# OSD_Shield.net
KiCad netlist of a schematic drawn in EAGLE
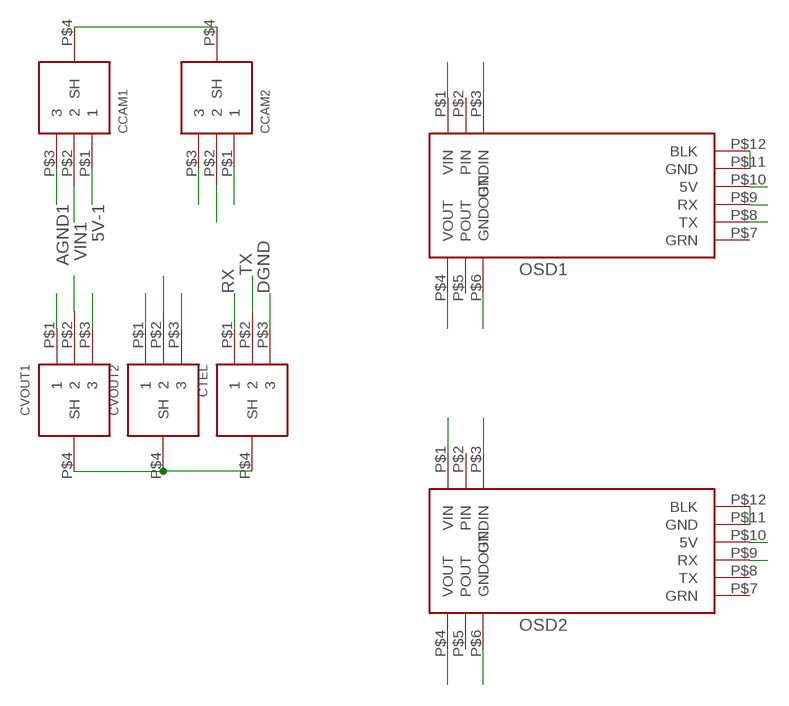
[diagram p0: schematic, sheet 1]

(export (version "E")
  (design (tool "Eeschema 10.0.6"))
  (components
    (comp (ref "CCAM1")
      (value "TRA3M")
      (footprint "eagle-import:TRA3M")
      (libsource (lib "eagle-import") (part "TRA3M"))
    )
    (comp (ref "CCAM2")
      (value "TRA3M")
      (footprint "eagle-import:TRA3M")
      (libsource (lib "eagle-import") (part "TRA3M"))
    )
    (comp (ref "CTEL")
      (value "TRA3MBARE")
      (footprint "eagle-import:TRA3M-BARE")
      (libsource (lib "eagle-import") (part "TRA3MBARE"))
    )
    (comp (ref "CVOUT1")
      (value "TRA3MBARE")
      (footprint "eagle-import:TRA3M-BARE")
      (libsource (lib "eagle-import") (part "TRA3MBARE"))
    )
    (comp (ref "CVOUT2")
      (value "TRA3MBARE")
      (footprint "eagle-import:TRA3M-BARE")
      (libsource (lib "eagle-import") (part "TRA3MBARE"))
    )
    (comp (ref "OSD1")
      (value "MINIM-OSD")
      (footprint "eagle-import:MINIM-OSD")
      (libsource (lib "eagle-import") (part "MINIM-OSD"))
    )
    (comp (ref "OSD2")
      (value "MINIM-OSD")
      (footprint "eagle-import:MINIM-OSD")
      (libsource (lib "eagle-import") (part "MINIM-OSD"))
    )
  )
  (nets
    (net (code "1") (name "/5V-1") (class "Default")
      (node (ref "CCAM1") (pin "P$1") (pinfunction "1_P$1") (pintype "bidirectional"))
      (node (ref "CVOUT1") (pin "P$1") (pinfunction "1_P$1") (pintype "bidirectional"))
      (node (ref "OSD1") (pin "P$10") (pinfunction "5V_P$10") (pintype "bidirectional"))
    )
    (net (code "2") (name "/5V-2") (class "Default")
      (node (ref "CCAM2") (pin "P$1") (pinfunction "1_P$1") (pintype "bidirectional"))
      (node (ref "CVOUT2") (pin "P$1") (pinfunction "1_P$1") (pintype "bidirectional"))
      (node (ref "OSD2") (pin "P$10") (pinfunction "5V_P$10") (pintype "bidirectional"))
    )
    (net (code "3") (name "/AGND1") (class "Default")
      (node (ref "CCAM1") (pin "P$3") (pinfunction "3_P$3") (pintype "bidirectional"))
      (node (ref "CVOUT1") (pin "P$3") (pinfunction "3_P$3") (pintype "bidirectional"))
      (node (ref "OSD1") (pin "P$3") (pinfunction "GNDIN_P$3") (pintype "bidirectional"))
      (node (ref "OSD1") (pin "P$6") (pinfunction "GNDOUT_P$6") (pintype "bidirectional"))
    )
    (net (code "4") (name "/AGND2") (class "Default")
      (node (ref "CCAM2") (pin "P$3") (pinfunction "3_P$3") (pintype "bidirectional"))
      (node (ref "CVOUT2") (pin "P$3") (pinfunction "3_P$3") (pintype "bidirectional"))
      (node (ref "OSD2") (pin "P$3") (pinfunction "GNDIN_P$3") (pintype "bidirectional"))
      (node (ref "OSD2") (pin "P$6") (pinfunction "GNDOUT_P$6") (pintype "bidirectional"))
    )
    (net (code "5") (name "/DGND") (class "Default")
      (node (ref "CTEL") (pin "P$3") (pinfunction "3_P$3") (pintype "bidirectional"))
      (node (ref "OSD1") (pin "P$11") (pinfunction "GND_P$11") (pintype "bidirectional"))
      (node (ref "OSD1") (pin "P$12") (pinfunction "BLK_P$12") (pintype "bidirectional"))
      (node (ref "OSD2") (pin "P$11") (pinfunction "GND_P$11") (pintype "bidirectional"))
      (node (ref "OSD2") (pin "P$12") (pinfunction "BLK_P$12") (pintype "bidirectional"))
    )
    (net (code "6") (name "/RX") (class "Default")
      (node (ref "CTEL") (pin "P$1") (pinfunction "1_P$1") (pintype "bidirectional"))
      (node (ref "OSD1") (pin "P$9") (pinfunction "RX_P$9") (pintype "bidirectional"))
      (node (ref "OSD2") (pin "P$9") (pinfunction "RX_P$9") (pintype "bidirectional"))
    )
    (net (code "7") (name "/SHLD") (class "Default")
      (node (ref "CCAM1") (pin "P$4") (pinfunction "SH_P$4") (pintype "bidirectional"))
      (node (ref "CCAM2") (pin "P$4") (pinfunction "SH_P$4") (pintype "bidirectional"))
      (node (ref "CTEL") (pin "P$4") (pinfunction "SH_P$4") (pintype "bidirectional"))
      (node (ref "CVOUT1") (pin "P$4") (pinfunction "SH_P$4") (pintype "bidirectional"))
      (node (ref "CVOUT2") (pin "P$4") (pinfunction "SH_P$4") (pintype "bidirectional"))
    )
    (net (code "8") (name "/TX") (class "Default")
      (node (ref "CTEL") (pin "P$2") (pinfunction "2_P$2") (pintype "bidirectional"))
      (node (ref "OSD1") (pin "P$8") (pinfunction "TX_P$8") (pintype "bidirectional"))
    )
    (net (code "9") (name "/VIN1") (class "Default")
      (node (ref "CCAM1") (pin "P$2") (pinfunction "2_P$2") (pintype "bidirectional"))
      (node (ref "OSD1") (pin "P$1") (pinfunction "VIN_P$1") (pintype "bidirectional"))
    )
    (net (code "10") (name "/VIN2") (class "Default")
      (node (ref "CCAM2") (pin "P$2") (pinfunction "2_P$2") (pintype "bidirectional"))
      (node (ref "OSD2") (pin "P$1") (pinfunction "VIN_P$1") (pintype "bidirectional"))
    )
    (net (code "11") (name "/VOUT1") (class "Default")
      (node (ref "CVOUT1") (pin "P$2") (pinfunction "2_P$2") (pintype "bidirectional"))
      (node (ref "OSD1") (pin "P$4") (pinfunction "VOUT_P$4") (pintype "bidirectional"))
    )
    (net (code "12") (name "/VOUT2") (class "Default")
      (node (ref "CVOUT2") (pin "P$2") (pinfunction "2_P$2") (pintype "bidirectional"))
      (node (ref "OSD2") (pin "P$4") (pinfunction "VOUT_P$4") (pintype "bidirectional"))
    )
    (net (code "13") (name "unconnected-(OSD1-GRN-PadP$7)") (class "Default")
      (node (ref "OSD1") (pin "P$7") (pinfunction "GRN_P$7") (pintype "bidirectional"))
    )
    (net (code "14") (name "unconnected-(OSD1-PIN-PadP$2)") (class "Default")
      (node (ref "OSD1") (pin "P$2") (pinfunction "PIN_P$2") (pintype "bidirectional"))
    )
    (net (code "15") (name "unconnected-(OSD1-POUT-PadP$5)") (class "Default")
      (node (ref "OSD1") (pin "P$5") (pinfunction "POUT_P$5") (pintype "bidirectional"))
    )
    (net (code "16") (name "unconnected-(OSD2-GRN-PadP$7)") (class "Default")
      (node (ref "OSD2") (pin "P$7") (pinfunction "GRN_P$7") (pintype "bidirectional"))
    )
    (net (code "17") (name "unconnected-(OSD2-PIN-PadP$2)") (class "Default")
      (node (ref "OSD2") (pin "P$2") (pinfunction "PIN_P$2") (pintype "bidirectional"))
    )
    (net (code "18") (name "unconnected-(OSD2-POUT-PadP$5)") (class "Default")
      (node (ref "OSD2") (pin "P$5") (pinfunction "POUT_P$5") (pintype "bidirectional"))
    )
    (net (code "19") (name "unconnected-(OSD2-TX-PadP$8)") (class "Default")
      (node (ref "OSD2") (pin "P$8") (pinfunction "TX_P$8") (pintype "bidirectional"))
    )
  )
)
